# Sch_Simetrica.net
KiCad netlist of a schematic drawn in Altium Designer
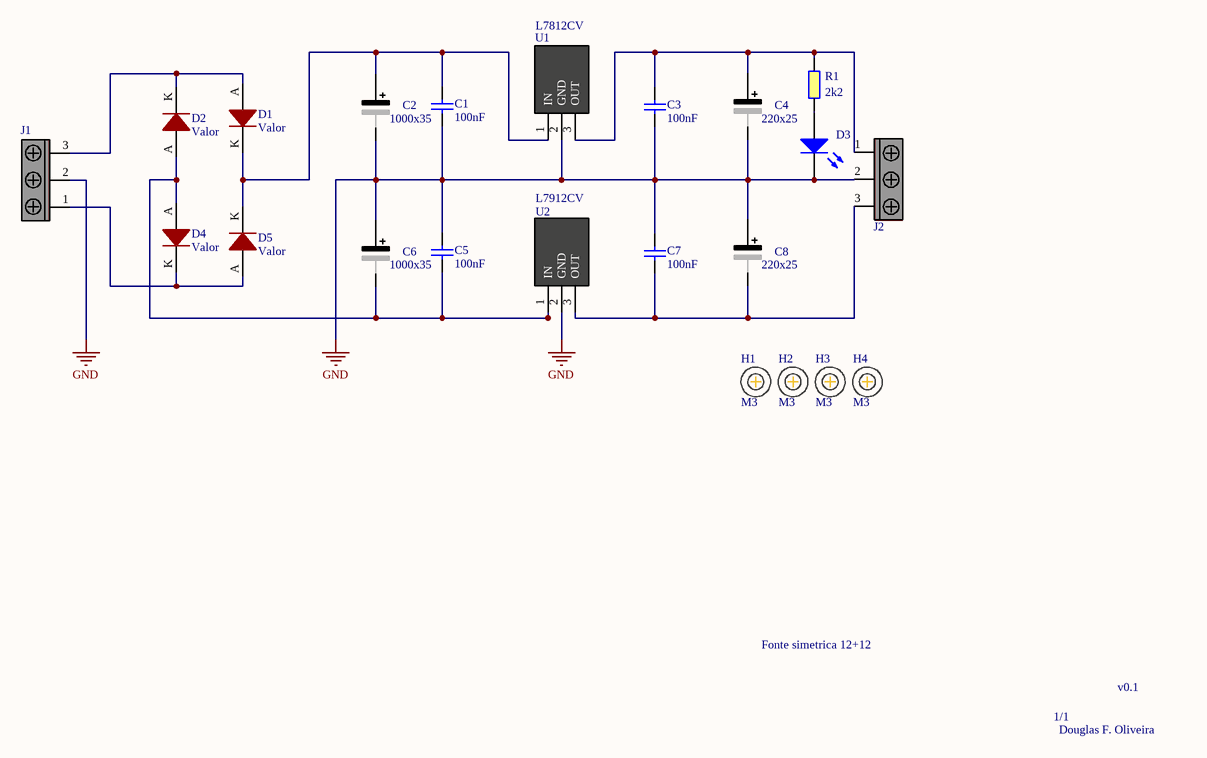
[diagram p0: Sch Simetrica.SchDoc]

(export (version "E")
  (design (tool "Eeschema 10.0.6"))
  (components
    (comp (ref "C1")
      (value "100nF")
      (footprint "RAD-0.2")
      (description "Capacitor")
      (libsource (lib "Basic Library") (part "C"))
    )
    (comp (ref "C2")
      (value "1000x35")
      (footprint "CAP ELETROLITICO 1000")
      (description "Polarized Capacitor (Radial)")
      (fields (field (name "PUBLISHER") "Altium Limited"))
      (libsource (lib "Componentes Basicos") (part "CAP POL"))
    )
    (comp (ref "C3")
      (value "100nF")
      (footprint "RAD-0.2")
      (description "Capacitor")
      (libsource (lib "Basic Library") (part "C"))
    )
    (comp (ref "C4")
      (value "220x25")
      (footprint "CAP ELETROLITICO 220")
      (description "Polarized Capacitor (Radial)")
      (fields (field (name "PUBLISHER") "Altium Limited"))
      (libsource (lib "Componentes Basicos") (part "CAP POL"))
    )
    (comp (ref "C5")
      (value "100nF")
      (footprint "RAD-0.2")
      (description "Capacitor")
      (libsource (lib "Basic Library") (part "C"))
    )
    (comp (ref "C6")
      (value "1000x35")
      (footprint "CAP ELETROLITICO 1000")
      (description "Polarized Capacitor (Radial)")
      (fields (field (name "PUBLISHER") "Altium Limited"))
      (libsource (lib "Componentes Basicos") (part "CAP POL"))
    )
    (comp (ref "C7")
      (value "100nF")
      (footprint "RAD-0.2")
      (description "Capacitor")
      (libsource (lib "Basic Library") (part "C"))
    )
    (comp (ref "C8")
      (value "220x25")
      (footprint "CAP ELETROLITICO 220")
      (description "Polarized Capacitor (Radial)")
      (fields (field (name "PUBLISHER") "Altium Limited"))
      (libsource (lib "Componentes Basicos") (part "CAP POL"))
    )
    (comp (ref "D1")
      (value "Valor")
      (footprint "DIOAD1405W58L465D235")
      (description "Retificador 1A 1000v")
      (fields (field (name "PUBLISHER") "Altium Limited"))
      (libsource (lib "Componentes Basicos") (part "DIODO 1N4007"))
    )
    (comp (ref "D2")
      (value "Valor")
      (footprint "DIOAD1405W58L465D235")
      (description "Retificador 1A 1000v")
      (fields (field (name "PUBLISHER") "Altium Limited"))
      (libsource (lib "Componentes Basicos") (part "DIODO 1N4007"))
    )
    (comp (ref "D3") (value "LED") (footprint "LED_3MM_RED") (libsource (lib "Basic Library") (part "LED")))
    (comp (ref "D4")
      (value "Valor")
      (footprint "DIOAD1405W58L465D235")
      (description "Retificador 1A 1000v")
      (fields (field (name "PUBLISHER") "Altium Limited"))
      (libsource (lib "Componentes Basicos") (part "DIODO 1N4007"))
    )
    (comp (ref "D5")
      (value "Valor")
      (footprint "DIOAD1405W58L465D235")
      (description "Retificador 1A 1000v")
      (fields (field (name "PUBLISHER") "Altium Limited"))
      (libsource (lib "Componentes Basicos") (part "DIODO 1N4007"))
    )
    (comp (ref "H1")
      (value "M3")
      (footprint "Parafuso M3")
      (libsource (lib "Meus Components") (part "Furo M3"))
    )
    (comp (ref "H2")
      (value "M3")
      (footprint "Parafuso M3")
      (libsource (lib "Meus Components") (part "Furo M3"))
    )
    (comp (ref "H3")
      (value "M3")
      (footprint "Parafuso M3")
      (libsource (lib "Meus Components") (part "Furo M3"))
    )
    (comp (ref "H4")
      (value "M3")
      (footprint "Parafuso M3")
      (libsource (lib "Meus Components") (part "Furo M3"))
    )
    (comp (ref "J1")
      (value "Conector 2v Phoenix")
      (footprint "Terminal block 5mm 3V")
      (description "Block, Terminal; 6 A; 63 V; 2.54 mm; 26 to 20 AWG; 2; Screw; Soldering; 1.5 kV")
      (fields
        (field (name "MANUFACTURER") "Phoenix Contact")
        (field (name "MANUFACTURER PART NUMBER") "1725656")
      )
      (libsource (lib "") (part "Conector 3v Phoenix_1_1"))
    )
    (comp (ref "J2")
      (value "Conector 2v Phoenix")
      (footprint "Terminal block 5mm 3V")
      (description "Block, Terminal; 6 A; 63 V; 2.54 mm; 26 to 20 AWG; 2; Screw; Soldering; 1.5 kV")
      (fields
        (field (name "MANUFACTURER") "Phoenix Contact")
        (field (name "MANUFACTURER PART NUMBER") "1725656")
      )
      (libsource (lib "Meus Components") (part "Conector 3v Phoenix_1"))
    )
    (comp (ref "R1")
      (value "2k2")
      (footprint "RES 1/4 PTH")
      (description "Resistor")
      (fields (field (name "PUBLISHER") "Altium Limited"))
      (libsource (lib "Componentes Basicos") (part "RESISTOR 1/4W"))
    )
    (comp (ref "U1")
      (value "L7812CV")
      (footprint "TO220")
      (description "L7905CV, Voltage Regulator, Negative 1.5A -5 V, 3-Pin TO-220")
      (fields
        (field (name "MOUSER PART NUMBER") "511-L7905CV")
        (field (name "MANUFACTURER_PART_NUMBER") "L7905CV")
      )
      (libsource (lib "Meus Components") (part "L78XXCV"))
    )
    (comp (ref "U2")
      (value "L7912CV")
      (footprint "TO220")
      (description "L7905CV, Voltage Regulator, Negative 1.5A -5 V, 3-Pin TO-220")
      (fields
        (field (name "MOUSER PART NUMBER") "511-L7905CV")
        (field (name "MANUFACTURER_PART_NUMBER") "L7905CV")
      )
      (libsource (lib "Meus Components") (part "L79XXCV"))
    )
  )
  (nets
    (net (code "1") (name "GND") (class "Default")
      (node (ref "C1") (pin "1") (pinfunction "1_1") (pintype "passive"))
      (node (ref "C2") (pin "2") (pinfunction "-_2") (pintype "passive"))
      (node (ref "C3") (pin "1") (pinfunction "1_1") (pintype "passive"))
      (node (ref "C4") (pin "2") (pinfunction "-_2") (pintype "passive"))
      (node (ref "C5") (pin "2") (pinfunction "2_2") (pintype "passive"))
      (node (ref "C6") (pin "1") (pinfunction "+_1") (pintype "passive"))
      (node (ref "C7") (pin "2") (pinfunction "2_2") (pintype "passive"))
      (node (ref "C8") (pin "1") (pinfunction "+_1") (pintype "passive"))
      (node (ref "D3") (pin "2") (pinfunction "K_2") (pintype "passive"))
      (node (ref "J1") (pin "2") (pinfunction "2_2") (pintype "passive"))
      (node (ref "J2") (pin "2") (pinfunction "2_2") (pintype "passive"))
      (node (ref "U1") (pin "2") (pinfunction "GND_2") (pintype "power_in"))
      (node (ref "U2") (pin "2") (pinfunction "GND_2") (pintype "power_in"))
    )
    (net (code "2") (name "Net-(C2-+)") (class "Default")
      (node (ref "C1") (pin "2") (pinfunction "2_2") (pintype "passive"))
      (node (ref "C2") (pin "1") (pinfunction "+_1") (pintype "passive"))
      (node (ref "D1") (pin "K") (pinfunction "2_K") (pintype "passive"))
      (node (ref "D5") (pin "K") (pinfunction "2_K") (pintype "passive"))
      (node (ref "U1") (pin "1") (pinfunction "IN_1") (pintype "power_in"))
    )
    (net (code "3") (name "Net-(C4-+)") (class "Default")
      (node (ref "C3") (pin "2") (pinfunction "2_2") (pintype "passive"))
      (node (ref "C4") (pin "1") (pinfunction "+_1") (pintype "passive"))
      (node (ref "J2") (pin "1") (pinfunction "1_1") (pintype "passive"))
      (node (ref "R1") (pin "2") (pinfunction "2_2") (pintype "passive"))
      (node (ref "U1") (pin "3") (pinfunction "OUT_3") (pintype "power_in"))
    )
    (net (code "4") (name "Net-(C6--)") (class "Default")
      (node (ref "C5") (pin "1") (pinfunction "1_1") (pintype "passive"))
      (node (ref "C6") (pin "2") (pinfunction "-_2") (pintype "passive"))
      (node (ref "D2") (pin "A") (pinfunction "1_A") (pintype "passive"))
      (node (ref "D4") (pin "A") (pinfunction "1_A") (pintype "passive"))
      (node (ref "U2") (pin "1") (pinfunction "IN_1") (pintype "power_in"))
    )
    (net (code "5") (name "Net-(C8--)") (class "Default")
      (node (ref "C7") (pin "1") (pinfunction "1_1") (pintype "passive"))
      (node (ref "C8") (pin "2") (pinfunction "-_2") (pintype "passive"))
      (node (ref "J2") (pin "3") (pinfunction "3_3") (pintype "passive"))
      (node (ref "U2") (pin "3") (pinfunction "OUT_3") (pintype "power_in"))
    )
    (net (code "6") (name "Net-(D1-1)") (class "Default")
      (node (ref "D1") (pin "A") (pinfunction "1_A") (pintype "passive"))
      (node (ref "D2") (pin "K") (pinfunction "2_K") (pintype "passive"))
      (node (ref "J1") (pin "3") (pinfunction "3_3") (pintype "passive"))
    )
    (net (code "7") (name "Net-(D3-A)") (class "Default")
      (node (ref "D3") (pin "1") (pinfunction "A_1") (pintype "passive"))
      (node (ref "R1") (pin "1") (pinfunction "1_1") (pintype "passive"))
    )
    (net (code "8") (name "Net-(D4-2)") (class "Default")
      (node (ref "D4") (pin "K") (pinfunction "2_K") (pintype "passive"))
      (node (ref "D5") (pin "A") (pinfunction "1_A") (pintype "passive"))
      (node (ref "J1") (pin "1") (pinfunction "1_1") (pintype "passive"))
    )
  )
)
